# DAC_ASCII.net
KiCad netlist of a schematic drawn in Altium Designer
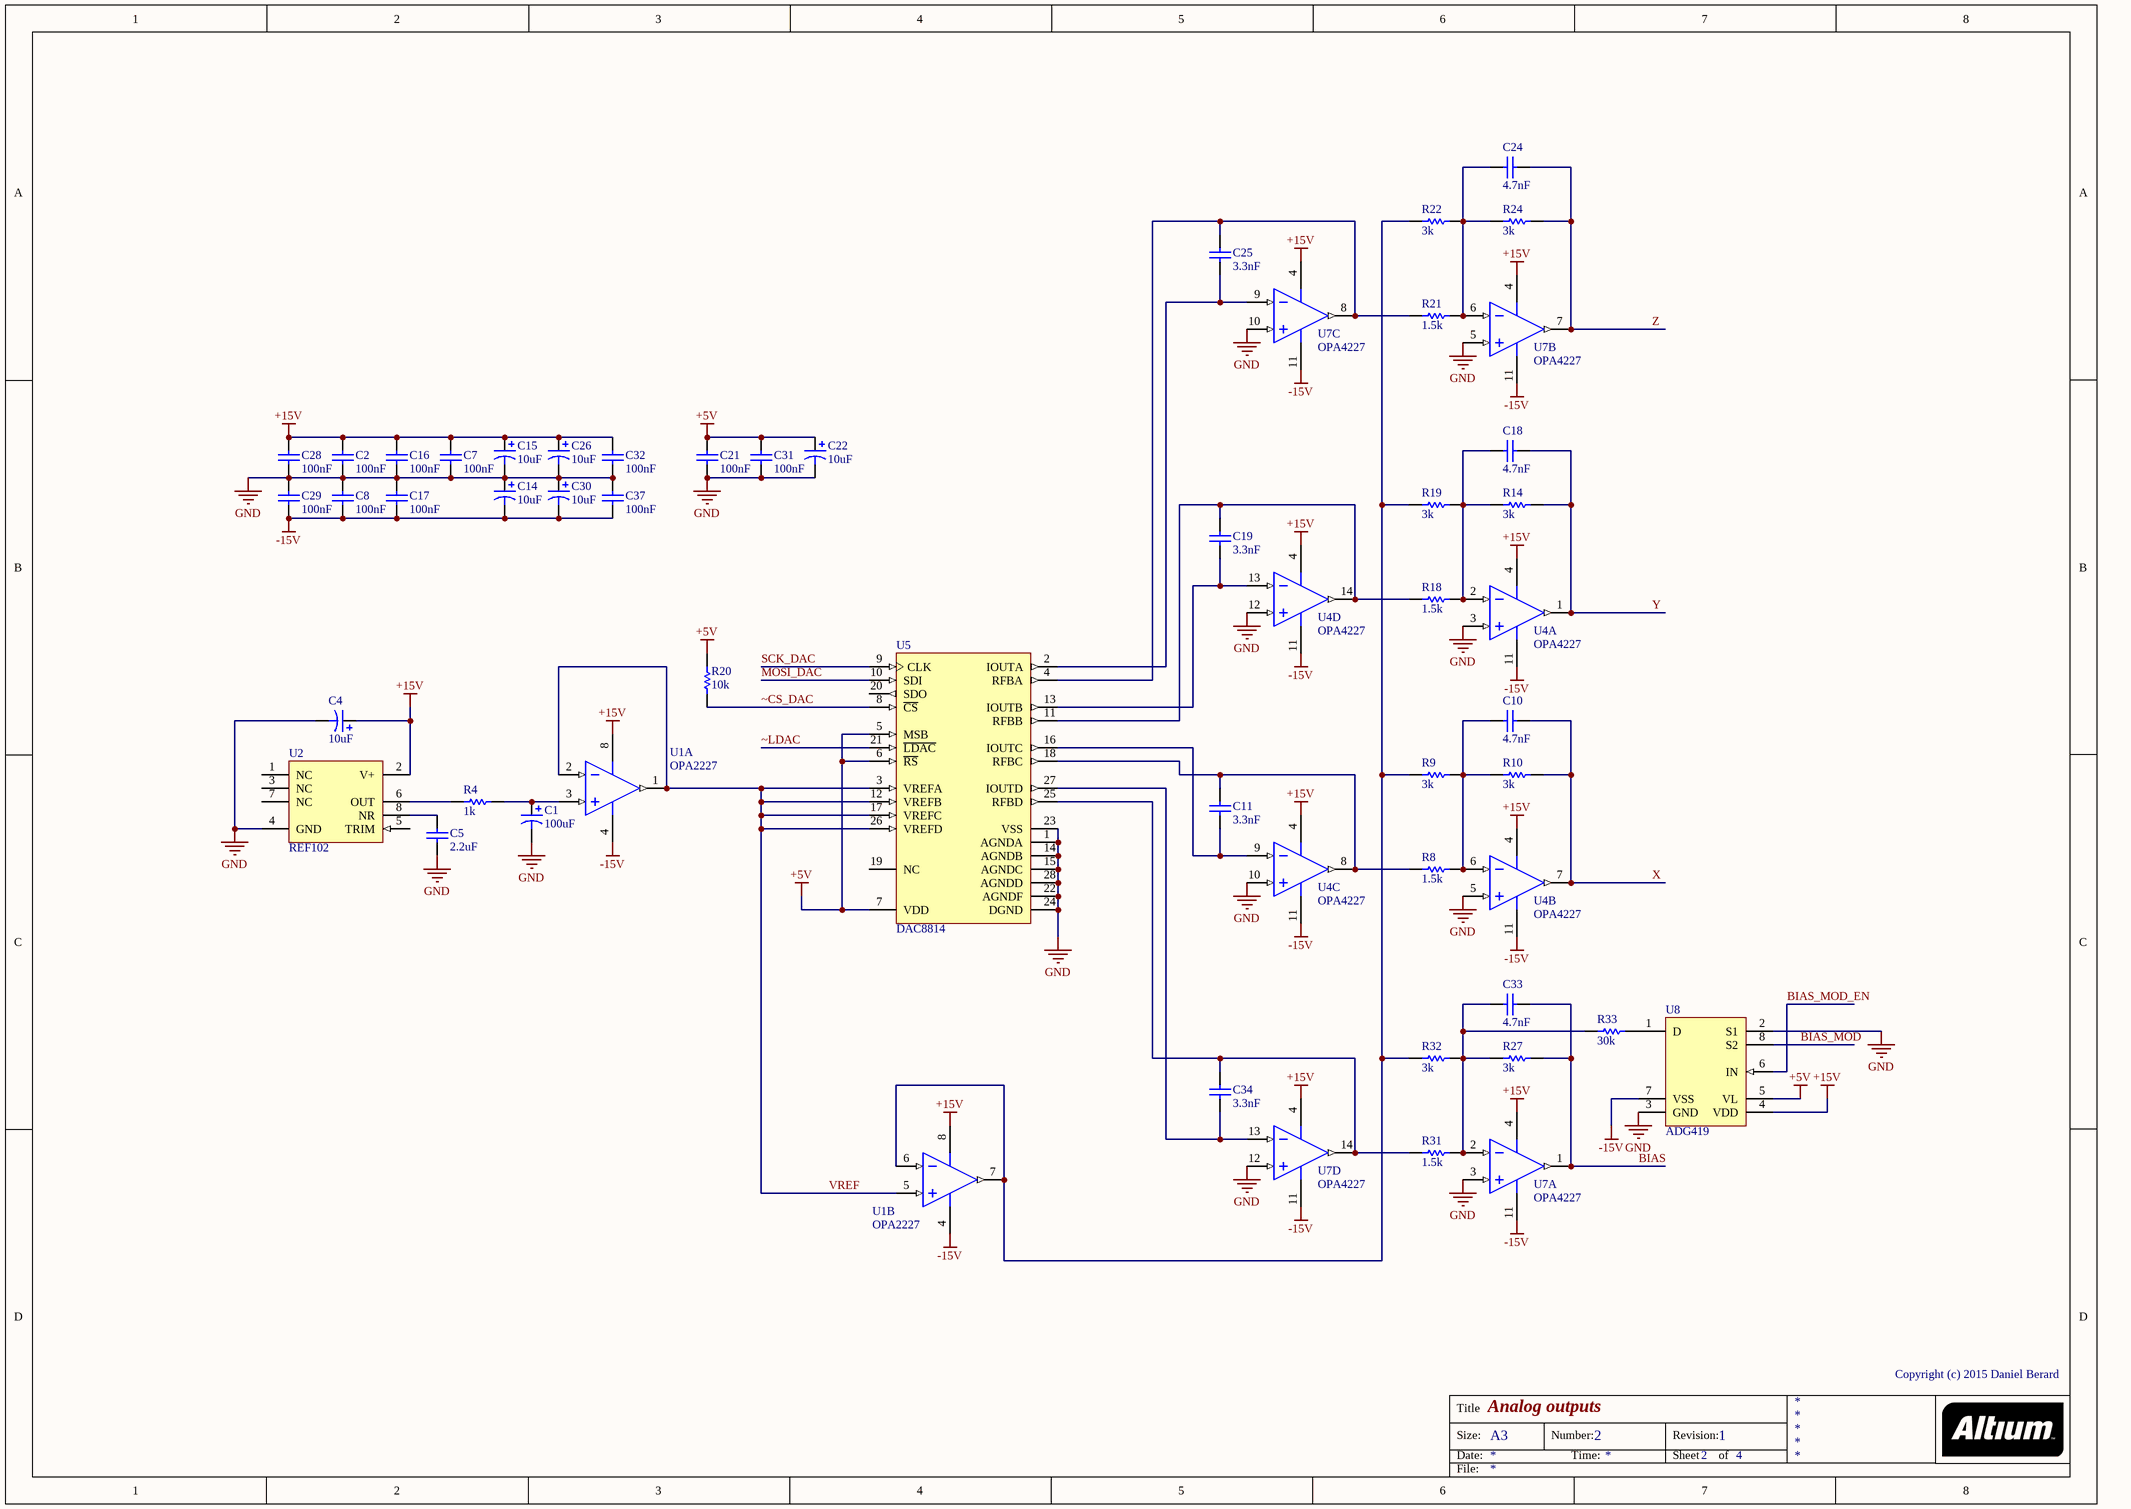
[diagram p0: DAC_ASCII.SchDoc]

(export (version "E")
  (design (tool "Eeschema 10.0.6"))
  (components
    (comp (ref "C1")
      (value "100uF")
      (footprint "7343")
      (description "Polarized Capacitor (Radial)")
      (fields (field (name "PUBLISHER") "Altium Limited"))
      (libsource (lib "Miscellaneous Devices") (part "Cap Pol1"))
    )
    (comp (ref "C2")
      (value "100nF")
      (footprint "6-0805_N")
      (description "Capacitor")
      (fields (field (name "PUBLISHER") "Altium Limited"))
      (libsource (lib "Miscellaneous Devices") (part "Cap"))
    )
    (comp (ref "C4")
      (value "10uF")
      (footprint "3528")
      (description "Polarized Capacitor (Radial)")
      (fields (field (name "PUBLISHER") "Altium Limited"))
      (libsource (lib "Miscellaneous Devices") (part "Cap Pol1"))
    )
    (comp (ref "C5")
      (value "2.2uF")
      (footprint "C1206")
      (description "Capacitor")
      (fields (field (name "PUBLISHER") "Altium Limited"))
      (libsource (lib "Miscellaneous Devices") (part "Cap"))
    )
    (comp (ref "C7")
      (value "100nF")
      (footprint "6-0805_N")
      (description "Capacitor")
      (fields (field (name "PUBLISHER") "Altium Limited"))
      (libsource (lib "Miscellaneous Devices") (part "Cap"))
    )
    (comp (ref "C8")
      (value "100nF")
      (footprint "6-0805_N")
      (description "Capacitor")
      (fields (field (name "PUBLISHER") "Altium Limited"))
      (libsource (lib "Miscellaneous Devices") (part "Cap"))
    )
    (comp (ref "C10")
      (value "4.7nF")
      (footprint "6-0805_N")
      (description "Capacitor")
      (fields (field (name "PUBLISHER") "Altium Limited"))
      (libsource (lib "Miscellaneous Devices") (part "Cap"))
    )
    (comp (ref "C11")
      (value "3.3nF")
      (footprint "6-0805_N")
      (description "Capacitor")
      (fields (field (name "PUBLISHER") "Altium Limited"))
      (libsource (lib "Miscellaneous Devices") (part "Cap"))
    )
    (comp (ref "C14")
      (value "10uF")
      (footprint "3528")
      (description "Polarized Capacitor (Radial)")
      (fields (field (name "PUBLISHER") "Altium Limited"))
      (libsource (lib "Miscellaneous Devices") (part "Cap Pol1"))
    )
    (comp (ref "C15")
      (value "10uF")
      (footprint "3528")
      (description "Polarized Capacitor (Radial)")
      (fields (field (name "PUBLISHER") "Altium Limited"))
      (libsource (lib "Miscellaneous Devices") (part "Cap Pol1"))
    )
    (comp (ref "C16")
      (value "100nF")
      (footprint "6-0805_N")
      (description "Capacitor")
      (fields (field (name "PUBLISHER") "Altium Limited"))
      (libsource (lib "Miscellaneous Devices") (part "Cap"))
    )
    (comp (ref "C17")
      (value "100nF")
      (footprint "6-0805_N")
      (description "Capacitor")
      (fields (field (name "PUBLISHER") "Altium Limited"))
      (libsource (lib "Miscellaneous Devices") (part "Cap"))
    )
    (comp (ref "C18")
      (value "4.7nF")
      (footprint "6-0805_N")
      (description "Capacitor")
      (fields (field (name "PUBLISHER") "Altium Limited"))
      (libsource (lib "Miscellaneous Devices") (part "Cap"))
    )
    (comp (ref "C19")
      (value "3.3nF")
      (footprint "6-0805_N")
      (description "Capacitor")
      (fields (field (name "PUBLISHER") "Altium Limited"))
      (libsource (lib "Miscellaneous Devices") (part "Cap"))
    )
    (comp (ref "C21")
      (value "100nF")
      (footprint "6-0805_N")
      (description "Capacitor")
      (fields (field (name "PUBLISHER") "Altium Limited"))
      (libsource (lib "Miscellaneous Devices") (part "Cap"))
    )
    (comp (ref "C22")
      (value "10uF")
      (footprint "6-0805_N")
      (description "Polarized Capacitor (Radial)")
      (fields (field (name "PUBLISHER") "Altium Limited"))
      (libsource (lib "Miscellaneous Devices") (part "Cap Pol1"))
    )
    (comp (ref "C24")
      (value "4.7nF")
      (footprint "6-0805_N")
      (description "Capacitor")
      (fields (field (name "PUBLISHER") "Altium Limited"))
      (libsource (lib "Miscellaneous Devices") (part "Cap"))
    )
    (comp (ref "C25")
      (value "3.3nF")
      (footprint "6-0805_N")
      (description "Capacitor")
      (fields (field (name "PUBLISHER") "Altium Limited"))
      (libsource (lib "Miscellaneous Devices") (part "Cap"))
    )
    (comp (ref "C26")
      (value "10uF")
      (footprint "3528")
      (description "Polarized Capacitor (Radial)")
      (fields (field (name "PUBLISHER") "Altium Limited"))
      (libsource (lib "Miscellaneous Devices") (part "Cap Pol1"))
    )
    (comp (ref "C28")
      (value "100nF")
      (footprint "6-0805_N")
      (description "Capacitor")
      (fields (field (name "PUBLISHER") "Altium Limited"))
      (libsource (lib "Miscellaneous Devices") (part "Cap"))
    )
    (comp (ref "C29")
      (value "100nF")
      (footprint "6-0805_N")
      (description "Capacitor")
      (fields (field (name "PUBLISHER") "Altium Limited"))
      (libsource (lib "Miscellaneous Devices") (part "Cap"))
    )
    (comp (ref "C30")
      (value "10uF")
      (footprint "3528")
      (description "Polarized Capacitor (Radial)")
      (fields (field (name "PUBLISHER") "Altium Limited"))
      (libsource (lib "Miscellaneous Devices") (part "Cap Pol1"))
    )
    (comp (ref "C31")
      (value "100nF")
      (footprint "6-0805_N")
      (description "Capacitor")
      (fields (field (name "PUBLISHER") "Altium Limited"))
      (libsource (lib "Miscellaneous Devices") (part "Cap"))
    )
    (comp (ref "C32")
      (value "100nF")
      (footprint "6-0805_N")
      (description "Capacitor")
      (fields (field (name "PUBLISHER") "Altium Limited"))
      (libsource (lib "Miscellaneous Devices") (part "Cap"))
    )
    (comp (ref "C33")
      (value "4.7nF")
      (footprint "6-0805_N")
      (description "Capacitor")
      (fields (field (name "PUBLISHER") "Altium Limited"))
      (libsource (lib "Miscellaneous Devices") (part "Cap"))
    )
    (comp (ref "C34")
      (value "3.3nF")
      (footprint "6-0805_N")
      (description "Capacitor")
      (fields (field (name "PUBLISHER") "Altium Limited"))
      (libsource (lib "Miscellaneous Devices") (part "Cap"))
    )
    (comp (ref "C37")
      (value "100nF")
      (footprint "6-0805_N")
      (description "Capacitor")
      (fields (field (name "PUBLISHER") "Altium Limited"))
      (libsource (lib "Miscellaneous Devices") (part "Cap"))
    )
    (comp (ref "R4")
      (value "1k")
      (footprint "6-0805_N")
      (description "Resistor")
      (fields (field (name "PUBLISHER") "Altium Limited"))
      (libsource (lib "Miscellaneous Devices") (part "Res1"))
    )
    (comp (ref "R8")
      (value "1.5k")
      (footprint "6-0805_N")
      (description "Resistor")
      (fields (field (name "PUBLISHER") "Altium Limited"))
      (libsource (lib "Miscellaneous Devices") (part "Res1"))
    )
    (comp (ref "R9")
      (value "3k")
      (footprint "6-0805_N")
      (description "Resistor")
      (fields (field (name "PUBLISHER") "Altium Limited"))
      (libsource (lib "Miscellaneous Devices") (part "Res1"))
    )
    (comp (ref "R10")
      (value "3k")
      (footprint "6-0805_N")
      (description "Resistor")
      (fields (field (name "PUBLISHER") "Altium Limited"))
      (libsource (lib "Miscellaneous Devices") (part "Res1"))
    )
    (comp (ref "R14")
      (value "3k")
      (footprint "6-0805_N")
      (description "Resistor")
      (fields (field (name "PUBLISHER") "Altium Limited"))
      (libsource (lib "Miscellaneous Devices") (part "Res1"))
    )
    (comp (ref "R18")
      (value "1.5k")
      (footprint "6-0805_N")
      (description "Resistor")
      (fields (field (name "PUBLISHER") "Altium Limited"))
      (libsource (lib "Miscellaneous Devices") (part "Res1"))
    )
    (comp (ref "R19")
      (value "3k")
      (footprint "6-0805_N")
      (description "Resistor")
      (fields (field (name "PUBLISHER") "Altium Limited"))
      (libsource (lib "Miscellaneous Devices") (part "Res1"))
    )
    (comp (ref "R20")
      (value "10k")
      (footprint "6-0805_N")
      (description "Resistor")
      (fields (field (name "PUBLISHER") "Altium Limited"))
      (libsource (lib "Miscellaneous Devices") (part "Res1"))
    )
    (comp (ref "R21")
      (value "1.5k")
      (footprint "6-0805_N")
      (description "Resistor")
      (fields (field (name "PUBLISHER") "Altium Limited"))
      (libsource (lib "Miscellaneous Devices") (part "Res1"))
    )
    (comp (ref "R22")
      (value "3k")
      (footprint "6-0805_N")
      (description "Resistor")
      (fields (field (name "PUBLISHER") "Altium Limited"))
      (libsource (lib "Miscellaneous Devices") (part "Res1"))
    )
    (comp (ref "R24")
      (value "3k")
      (footprint "6-0805_N")
      (description "Resistor")
      (fields (field (name "PUBLISHER") "Altium Limited"))
      (libsource (lib "Miscellaneous Devices") (part "Res1"))
    )
    (comp (ref "R27")
      (value "3k")
      (footprint "6-0805_N")
      (description "Resistor")
      (fields (field (name "PUBLISHER") "Altium Limited"))
      (libsource (lib "Miscellaneous Devices") (part "Res1"))
    )
    (comp (ref "R31")
      (value "1.5k")
      (footprint "6-0805_N")
      (description "Resistor")
      (fields (field (name "PUBLISHER") "Altium Limited"))
      (libsource (lib "Miscellaneous Devices") (part "Res1"))
    )
    (comp (ref "R32")
      (value "3k")
      (footprint "6-0805_N")
      (description "Resistor")
      (fields (field (name "PUBLISHER") "Altium Limited"))
      (libsource (lib "Miscellaneous Devices") (part "Res1"))
    )
    (comp (ref "R33")
      (value "30k")
      (footprint "6-0805_N")
      (description "Resistor")
      (fields (field (name "PUBLISHER") "Altium Limited"))
      (libsource (lib "Miscellaneous Devices") (part "Res1"))
    )
    (comp (ref "U1")
      (value "OPA2227")
      (footprint "ADI-R-8_M")
      (fields
        (field (name "MANUFACTURER") "Analog Devices")
        (field (name "GENERIC PART NUMBER") "AD8676")
        (field (name "PARTNUMBER") "AD8676BRZ")
      )
      (libsource (lib "Altium Content Vault") (part "CMP-0384-01147-2"))
    )
    (comp (ref "U2")
      (value "REF102")
      (footprint "182H_N")
      (description "Precision Voltage Reference")
      (fields (field (name "PUBLISHER") "Altium Limited"))
      (libsource (lib "BB Power Mgt Voltage Reference") (part "REF102AU"))
    )
    (comp (ref "U4")
      (value "OPA4227")
      (footprint "TI-D14_M")
      (fields (field (name "PARTNUMBER") "OPA4227UA/2K5") (field (name "MANUFACTURER") "Texas Instruments"))
      (libsource (lib "Altium Content Vault") (part "CMP-0272-00152-2"))
    )
    (comp (ref "U5")
      (value "DAC8814")
      (footprint "TI-DB28_L")
      (fields (field (name "MANUFACTURER") "Texas Instruments") (field (name "PARTNUMBER") "DAC8814ICDBTG4"))
      (libsource (lib "Altium Content Vault") (part "CMP-0004-00286-1"))
    )
    (comp (ref "U7")
      (value "OPA4227")
      (footprint "TI-D14_M")
      (fields (field (name "PARTNUMBER") "OPA4227UA/2K5") (field (name "MANUFACTURER") "Texas Instruments"))
      (libsource (lib "Altium Content Vault") (part "CMP-0272-00152-2"))
    )
    (comp (ref "U8")
      (value "ADG419")
      (footprint "ADI-RM-8_N")
      (description "LC2MOS Precision Mini-DIP Analog Switches, 25 Ohm Ron, 8-pin SOP (RM-8), Tube")
      (fields (field (name "MANUFACTURER") "Analog Devices") (field (name "PARTNUMBER") "ADG419BRMZ"))
      (libsource (lib "Altium Content Vault") (part "CMP-0792-00196-1"))
    )
  )
  (nets
    (net (code "1") (name "+5V") (class "Default")
      (node (ref "C21") (pin "2") (pinfunction "2_2") (pintype "passive"))
      (node (ref "C22") (pin "1") (pinfunction "1_1") (pintype "passive"))
      (node (ref "C31") (pin "2") (pinfunction "2_2") (pintype "passive"))
      (node (ref "R20") (pin "2") (pinfunction "2_2") (pintype "passive"))
      (node (ref "U5") (pin "5") (pinfunction "MSB_5") (pintype "input"))
      (node (ref "U5") (pin "6") (pinfunction "~{RS}_6") (pintype "input"))
      (node (ref "U5") (pin "7") (pinfunction "VDD_7") (pintype "power_in"))
      (node (ref "U8") (pin "5") (pinfunction "VL_5") (pintype "power_in"))
    )
    (net (code "2") (name "+15V") (class "Default")
      (node (ref "C15") (pin "1") (pinfunction "1_1") (pintype "passive"))
      (node (ref "C16") (pin "2") (pinfunction "2_2") (pintype "passive"))
      (node (ref "C2") (pin "2") (pinfunction "2_2") (pintype "passive"))
      (node (ref "C26") (pin "1") (pinfunction "1_1") (pintype "passive"))
      (node (ref "C28") (pin "2") (pinfunction "2_2") (pintype "passive"))
      (node (ref "C32") (pin "2") (pinfunction "2_2") (pintype "passive"))
      (node (ref "C4") (pin "1") (pinfunction "1_1") (pintype "passive"))
      (node (ref "C7") (pin "1") (pinfunction "1_1") (pintype "passive"))
      (node (ref "U1") (pin "8") (pinfunction "+V_8") (pintype "power_in"))
      (node (ref "U2") (pin "2") (pinfunction "V+_2") (pintype "power_in"))
      (node (ref "U4") (pin "4") (pinfunction "V+_4") (pintype "power_in"))
      (node (ref "U7") (pin "4") (pinfunction "V+_4") (pintype "power_in"))
      (node (ref "U8") (pin "4") (pinfunction "VDD_4") (pintype "power_in"))
    )
    (net (code "3") (name "-15V") (class "Default")
      (node (ref "C14") (pin "2") (pinfunction "2_2") (pintype "passive"))
      (node (ref "C17") (pin "1") (pinfunction "1_1") (pintype "passive"))
      (node (ref "C29") (pin "1") (pinfunction "1_1") (pintype "passive"))
      (node (ref "C30") (pin "2") (pinfunction "2_2") (pintype "passive"))
      (node (ref "C37") (pin "1") (pinfunction "1_1") (pintype "passive"))
      (node (ref "C8") (pin "1") (pinfunction "1_1") (pintype "passive"))
      (node (ref "U1") (pin "4") (pinfunction "-V_4") (pintype "power_in"))
      (node (ref "U4") (pin "11") (pinfunction "V-_11") (pintype "power_in"))
      (node (ref "U7") (pin "11") (pinfunction "V-_11") (pintype "power_in"))
      (node (ref "U8") (pin "7") (pinfunction "VSS_7") (pintype "power_in"))
    )
    (net (code "4") (name "/BIAS") (class "Default")
      (node (ref "C33") (pin "2") (pinfunction "2_2") (pintype "passive"))
      (node (ref "R27") (pin "2") (pinfunction "2_2") (pintype "passive"))
      (node (ref "U7") (pin "1") (pinfunction "OUT_A_1") (pintype "output"))
    )
    (net (code "5") (name "/BIAS_MOD") (class "Default")
      (node (ref "U8") (pin "8") (pinfunction "S2_8") (pintype "passive"))
    )
    (net (code "6") (name "/BIAS_MOD_EN") (class "Default")
      (node (ref "U8") (pin "6") (pinfunction "IN_6") (pintype "input"))
    )
    (net (code "7") (name "/MOSI_DAC") (class "Default")
      (node (ref "U5") (pin "10") (pinfunction "SDI_10") (pintype "input"))
    )
    (net (code "8") (name "/SCK_DAC") (class "Default")
      (node (ref "U5") (pin "9") (pinfunction "CLK_9") (pintype "input"))
    )
    (net (code "9") (name "/VREF") (class "Default")
      (node (ref "U1") (pin "1") (pinfunction "OUT_A_1") (pintype "output"))
      (node (ref "U1") (pin "2") (pinfunction "-IN_A_2") (pintype "input"))
      (node (ref "U1") (pin "5") (pinfunction "+IN_B_5") (pintype "input"))
      (node (ref "U5") (pin "12") (pinfunction "VREFB_12") (pintype "input"))
      (node (ref "U5") (pin "17") (pinfunction "VREFC_17") (pintype "input"))
      (node (ref "U5") (pin "26") (pinfunction "VREFD_26") (pintype "input"))
      (node (ref "U5") (pin "3") (pinfunction "VREFA_3") (pintype "input"))
    )
    (net (code "10") (name "/X") (class "Default")
      (node (ref "C10") (pin "2") (pinfunction "2_2") (pintype "passive"))
      (node (ref "R10") (pin "2") (pinfunction "2_2") (pintype "passive"))
      (node (ref "U4") (pin "7") (pinfunction "OUT_B_7") (pintype "output"))
    )
    (net (code "11") (name "/Y") (class "Default")
      (node (ref "C18") (pin "2") (pinfunction "2_2") (pintype "passive"))
      (node (ref "R14") (pin "2") (pinfunction "2_2") (pintype "passive"))
      (node (ref "U4") (pin "1") (pinfunction "OUT_A_1") (pintype "output"))
    )
    (net (code "12") (name "/Z") (class "Default")
      (node (ref "C24") (pin "2") (pinfunction "2_2") (pintype "passive"))
      (node (ref "R24") (pin "2") (pinfunction "2_2") (pintype "passive"))
      (node (ref "U7") (pin "7") (pinfunction "OUT_B_7") (pintype "output"))
    )
    (net (code "13") (name "/~CS_DAC") (class "Default")
      (node (ref "R20") (pin "1") (pinfunction "1_1") (pintype "passive"))
      (node (ref "U5") (pin "8") (pinfunction "~{CS}_8") (pintype "input"))
    )
    (net (code "14") (name "/~LDAC") (class "Default")
      (node (ref "U5") (pin "21") (pinfunction "~{LDAC}_21") (pintype "input"))
    )
    (net (code "15") (name "GND") (class "Default")
      (node (ref "C1") (pin "2") (pinfunction "2_2") (pintype "passive"))
      (node (ref "C14") (pin "1") (pinfunction "1_1") (pintype "passive"))
      (node (ref "C15") (pin "2") (pinfunction "2_2") (pintype "passive"))
      (node (ref "C16") (pin "1") (pinfunction "1_1") (pintype "passive"))
      (node (ref "C17") (pin "2") (pinfunction "2_2") (pintype "passive"))
      (node (ref "C2") (pin "1") (pinfunction "1_1") (pintype "passive"))
      (node (ref "C21") (pin "1") (pinfunction "1_1") (pintype "passive"))
      (node (ref "C22") (pin "2") (pinfunction "2_2") (pintype "passive"))
      (node (ref "C26") (pin "2") (pinfunction "2_2") (pintype "passive"))
      (node (ref "C28") (pin "1") (pinfunction "1_1") (pintype "passive"))
      (node (ref "C29") (pin "2") (pinfunction "2_2") (pintype "passive"))
      (node (ref "C30") (pin "1") (pinfunction "1_1") (pintype "passive"))
      (node (ref "C31") (pin "1") (pinfunction "1_1") (pintype "passive"))
      (node (ref "C32") (pin "1") (pinfunction "1_1") (pintype "passive"))
      (node (ref "C37") (pin "2") (pinfunction "2_2") (pintype "passive"))
      (node (ref "C4") (pin "2") (pinfunction "2_2") (pintype "passive"))
      (node (ref "C5") (pin "2") (pinfunction "2_2") (pintype "passive"))
      (node (ref "C7") (pin "2") (pinfunction "2_2") (pintype "passive"))
      (node (ref "C8") (pin "2") (pinfunction "2_2") (pintype "passive"))
      (node (ref "U2") (pin "4") (pinfunction "GND_4") (pintype "power_in"))
      (node (ref "U4") (pin "10") (pinfunction "IN_C+_10") (pintype "input"))
      (node (ref "U4") (pin "12") (pinfunction "IN_D+_12") (pintype "input"))
      (node (ref "U4") (pin "3") (pinfunction "IN_A+_3") (pintype "input"))
      (node (ref "U4") (pin "5") (pinfunction "IN_B+_5") (pintype "input"))
      (node (ref "U5") (pin "1") (pinfunction "AGNDA_1") (pintype "power_in"))
      (node (ref "U5") (pin "14") (pinfunction "AGNDB_14") (pintype "power_in"))
      (node (ref "U5") (pin "15") (pinfunction "AGNDC_15") (pintype "power_in"))
      (node (ref "U5") (pin "22") (pinfunction "AGNDF_22") (pintype "power_in"))
      (node (ref "U5") (pin "23") (pinfunction "VSS_23") (pintype "passive"))
      (node (ref "U5") (pin "24") (pinfunction "DGND_24") (pintype "power_in"))
      (node (ref "U5") (pin "28") (pinfunction "AGNDD_28") (pintype "power_in"))
      (node (ref "U7") (pin "10") (pinfunction "IN_C+_10") (pintype "input"))
      (node (ref "U7") (pin "12") (pinfunction "IN_D+_12") (pintype "input"))
      (node (ref "U7") (pin "3") (pinfunction "IN_A+_3") (pintype "input"))
      (node (ref "U7") (pin "5") (pinfunction "IN_B+_5") (pintype "input"))
      (node (ref "U8") (pin "2") (pinfunction "S1_2") (pintype "passive"))
      (node (ref "U8") (pin "3") (pinfunction "GND_3") (pintype "power_in"))
    )
    (net (code "16") (name "Net-(U1A-+IN_A)") (class "Default")
      (node (ref "C1") (pin "1") (pinfunction "1_1") (pintype "passive"))
      (node (ref "R4") (pin "2") (pinfunction "2_2") (pintype "passive"))
      (node (ref "U1") (pin "3") (pinfunction "+IN_A_3") (pintype "input"))
    )
    (net (code "17") (name "Net-(U1B--IN_B)") (class "Default")
      (node (ref "R19") (pin "1") (pinfunction "1_1") (pintype "passive"))
      (node (ref "R22") (pin "1") (pinfunction "1_1") (pintype "passive"))
      (node (ref "R32") (pin "1") (pinfunction "1_1") (pintype "passive"))
      (node (ref "R9") (pin "1") (pinfunction "1_1") (pintype "passive"))
      (node (ref "U1") (pin "6") (pinfunction "-IN_B_6") (pintype "input"))
      (node (ref "U1") (pin "7") (pinfunction "OUT_B_7") (pintype "output"))
    )
    (net (code "18") (name "Net-(U2-NR)") (class "Default")
      (node (ref "C5") (pin "1") (pinfunction "1_1") (pintype "passive"))
      (node (ref "U2") (pin "8") (pinfunction "NR_8") (pintype "passive"))
    )
    (net (code "19") (name "Net-(U2-OUT)") (class "Default")
      (node (ref "R4") (pin "1") (pinfunction "1_1") (pintype "passive"))
      (node (ref "U2") (pin "6") (pinfunction "OUT_6") (pintype "power_in"))
    )
    (net (code "20") (name "Net-(U4A-IN_A-)") (class "Default")
      (node (ref "C18") (pin "1") (pinfunction "1_1") (pintype "passive"))
      (node (ref "R14") (pin "1") (pinfunction "1_1") (pintype "passive"))
      (node (ref "R18") (pin "2") (pinfunction "2_2") (pintype "passive"))
      (node (ref "R19") (pin "2") (pinfunction "2_2") (pintype "passive"))
      (node (ref "U4") (pin "2") (pinfunction "IN_A-_2") (pintype "input"))
    )
    (net (code "21") (name "Net-(U4B-IN_B-)") (class "Default")
      (node (ref "C10") (pin "1") (pinfunction "1_1") (pintype "passive"))
      (node (ref "R10") (pin "1") (pinfunction "1_1") (pintype "passive"))
      (node (ref "R8") (pin "2") (pinfunction "2_2") (pintype "passive"))
      (node (ref "R9") (pin "2") (pinfunction "2_2") (pintype "passive"))
      (node (ref "U4") (pin "6") (pinfunction "IN_B-_6") (pintype "input"))
    )
    (net (code "22") (name "Net-(U4C-IN_C-)") (class "Default")
      (node (ref "C11") (pin "1") (pinfunction "1_1") (pintype "passive"))
      (node (ref "U4") (pin "9") (pinfunction "IN_C-_9") (pintype "input"))
      (node (ref "U5") (pin "16") (pinfunction "IOUTC_16") (pintype "output"))
    )
    (net (code "23") (name "Net-(U4C-OUT_C)") (class "Default")
      (node (ref "C11") (pin "2") (pinfunction "2_2") (pintype "passive"))
      (node (ref "R8") (pin "1") (pinfunction "1_1") (pintype "passive"))
      (node (ref "U4") (pin "8") (pinfunction "OUT_C_8") (pintype "output"))
      (node (ref "U5") (pin "18") (pinfunction "RFBC_18") (pintype "output"))
    )
    (net (code "24") (name "Net-(U4D-IN_D-)") (class "Default")
      (node (ref "C19") (pin "1") (pinfunction "1_1") (pintype "passive"))
      (node (ref "U4") (pin "13") (pinfunction "IN_D-_13") (pintype "input"))
      (node (ref "U5") (pin "13") (pinfunction "IOUTB_13") (pintype "output"))
    )
    (net (code "25") (name "Net-(U4D-OUT_D)") (class "Default")
      (node (ref "C19") (pin "2") (pinfunction "2_2") (pintype "passive"))
      (node (ref "R18") (pin "1") (pinfunction "1_1") (pintype "passive"))
      (node (ref "U4") (pin "14") (pinfunction "OUT_D_14") (pintype "output"))
      (node (ref "U5") (pin "11") (pinfunction "RFBB_11") (pintype "output"))
    )
    (net (code "26") (name "Net-(U5-IOUTA)") (class "Default")
      (node (ref "C25") (pin "1") (pinfunction "1_1") (pintype "passive"))
      (node (ref "U5") (pin "2") (pinfunction "IOUTA_2") (pintype "output"))
      (node (ref "U7") (pin "9") (pinfunction "IN_C-_9") (pintype "input"))
    )
    (net (code "27") (name "Net-(U5-IOUTD)") (class "Default")
      (node (ref "C34") (pin "1") (pinfunction "1_1") (pintype "passive"))
      (node (ref "U5") (pin "27") (pinfunction "IOUTD_27") (pintype "output"))
      (node (ref "U7") (pin "13") (pinfunction "IN_D-_13") (pintype "input"))
    )
    (net (code "28") (name "Net-(U5-RFBA)") (class "Default")
      (node (ref "C25") (pin "2") (pinfunction "2_2") (pintype "passive"))
      (node (ref "R21") (pin "1") (pinfunction "1_1") (pintype "passive"))
      (node (ref "U5") (pin "4") (pinfunction "RFBA_4") (pintype "output"))
      (node (ref "U7") (pin "8") (pinfunction "OUT_C_8") (pintype "output"))
    )
    (net (code "29") (name "Net-(U5-RFBD)") (class "Default")
      (node (ref "C34") (pin "2") (pinfunction "2_2") (pintype "passive"))
      (node (ref "R31") (pin "1") (pinfunction "1_1") (pintype "passive"))
      (node (ref "U5") (pin "25") (pinfunction "RFBD_25") (pintype "output"))
      (node (ref "U7") (pin "14") (pinfunction "OUT_D_14") (pintype "output"))
    )
    (net (code "30") (name "Net-(U7A-IN_A-)") (class "Default")
      (node (ref "C33") (pin "1") (pinfunction "1_1") (pintype "passive"))
      (node (ref "R27") (pin "1") (pinfunction "1_1") (pintype "passive"))
      (node (ref "R31") (pin "2") (pinfunction "2_2") (pintype "passive"))
      (node (ref "R32") (pin "2") (pinfunction "2_2") (pintype "passive"))
      (node (ref "R33") (pin "1") (pinfunction "1_1") (pintype "passive"))
      (node (ref "U7") (pin "2") (pinfunction "IN_A-_2") (pintype "input"))
    )
    (net (code "31") (name "Net-(U7B-IN_B-)") (class "Default")
      (node (ref "C24") (pin "1") (pinfunction "1_1") (pintype "passive"))
      (node (ref "R21") (pin "2") (pinfunction "2_2") (pintype "passive"))
      (node (ref "R22") (pin "2") (pinfunction "2_2") (pintype "passive"))
      (node (ref "R24") (pin "1") (pinfunction "1_1") (pintype "passive"))
      (node (ref "U7") (pin "6") (pinfunction "IN_B-_6") (pintype "input"))
    )
    (net (code "32") (name "Net-(U8-D)") (class "Default")
      (node (ref "R33") (pin "2") (pinfunction "2_2") (pintype "passive"))
      (node (ref "U8") (pin "1") (pinfunction "D_1") (pintype "passive"))
    )
    (net (code "33") (name "unconnected-(U2-NC-Pad1)") (class "Default")
      (node (ref "U2") (pin "1") (pinfunction "NC_1") (pintype "passive"))
    )
    (net (code "34") (name "unconnected-(U2-NC-Pad3)") (class "Default")
      (node (ref "U2") (pin "3") (pinfunction "NC_3") (pintype "passive"))
    )
    (net (code "35") (name "unconnected-(U2-NC-Pad7)") (class "Default")
      (node (ref "U2") (pin "7") (pinfunction "NC_7") (pintype "passive"))
    )
    (net (code "36") (name "unconnected-(U2-TRIM-Pad5)") (class "Default")
      (node (ref "U2") (pin "5") (pinfunction "TRIM_5") (pintype "input"))
    )
    (net (code "37") (name "unconnected-(U5-NC-Pad19)") (class "Default")
      (node (ref "U5") (pin "19") (pinfunction "NC_19") (pintype "passive"))
    )
    (net (code "38") (name "unconnected-(U5-SDO-Pad20)") (class "Default")
      (node (ref "U5") (pin "20") (pinfunction "SDO_20") (pintype "output"))
    )
  )
)
